# relay-v1.net
KiCad netlist of a schematic drawn in EAGLE
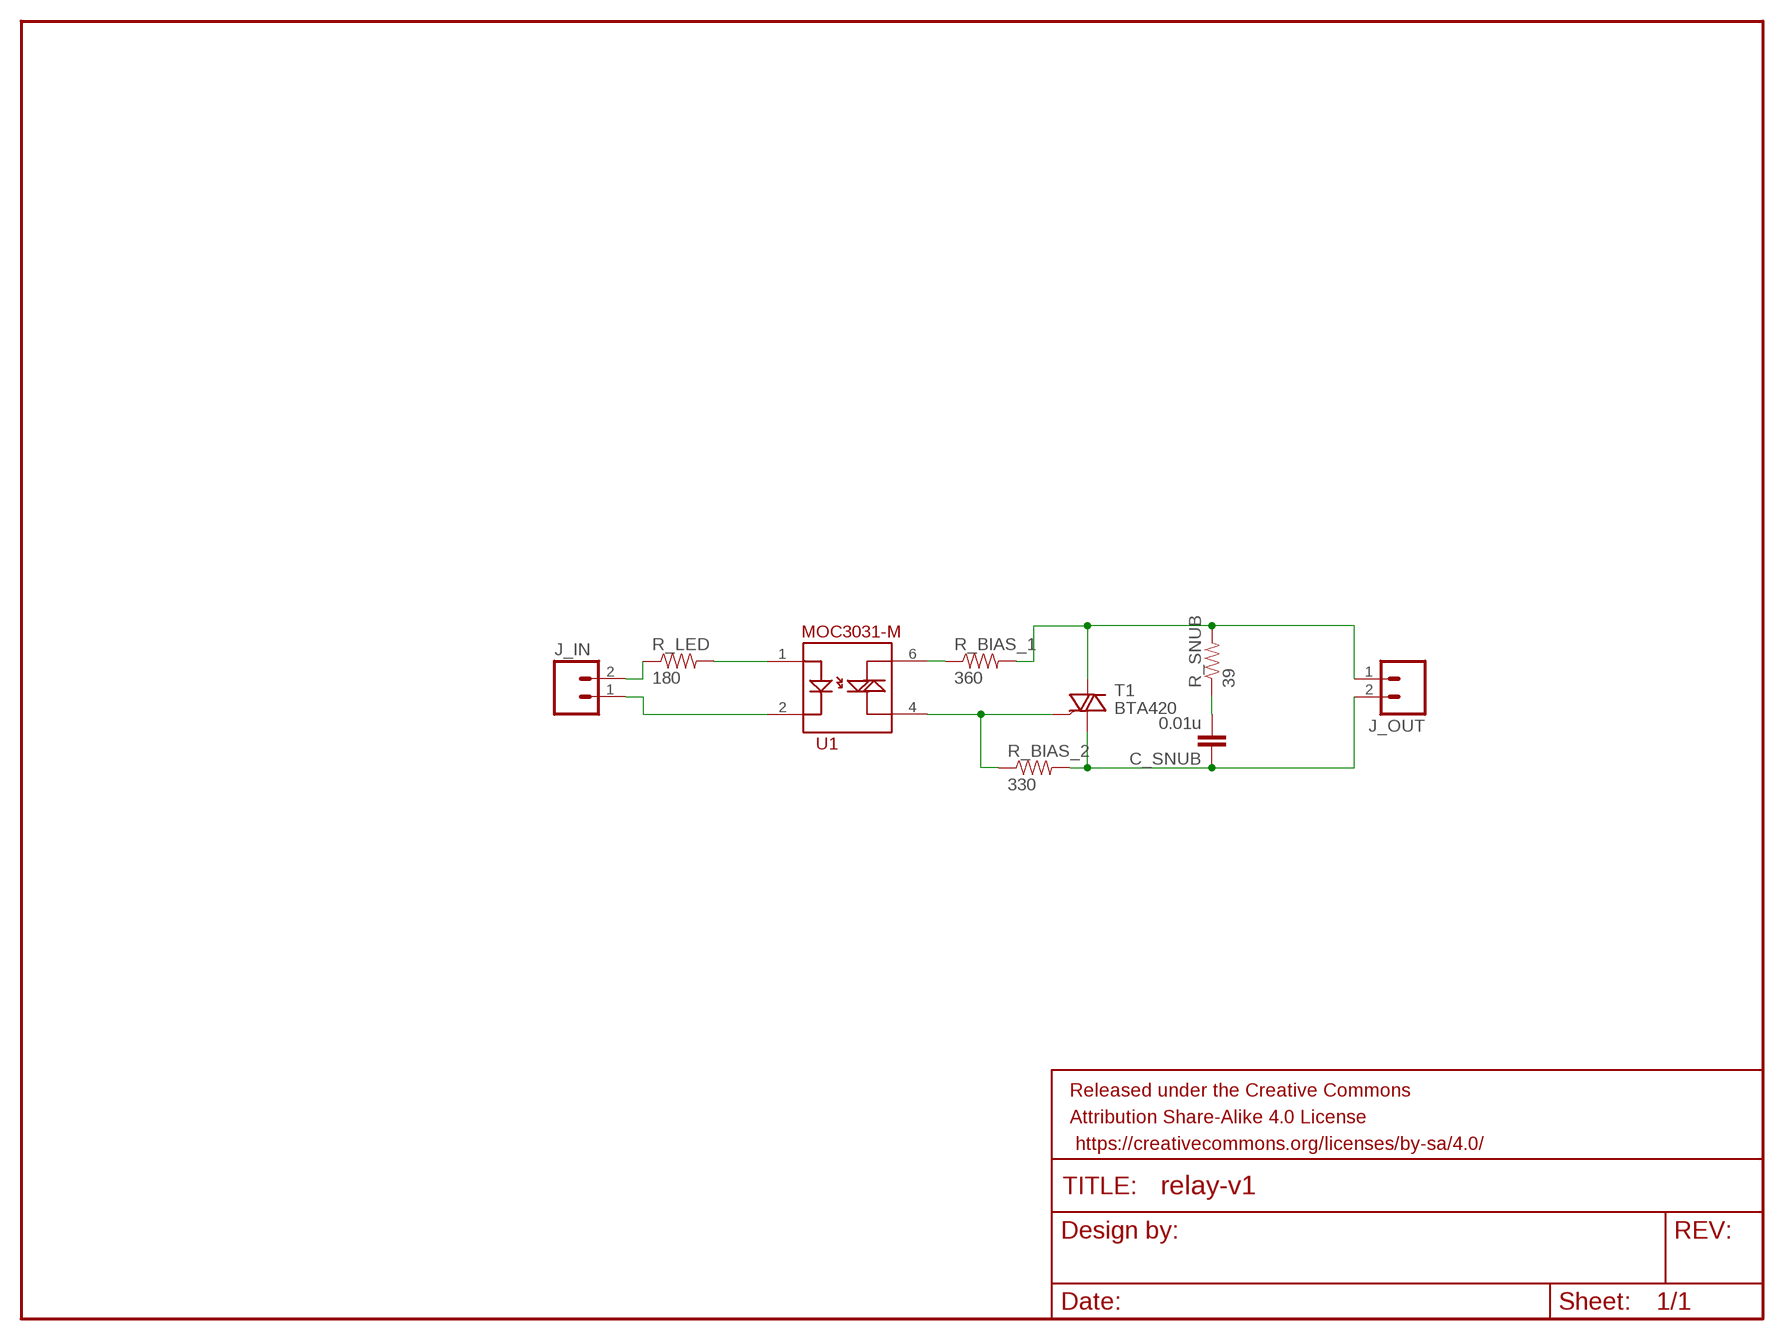
[diagram p0: schematic, sheet 1]

(export (version "E")
  (design (tool "Eeschema 10.0.6"))
  (components
    (comp (ref "C_SNUB")
      (value "0.01u")
      (footprint "eagle-import:CAP-PTH-SMALLEZ")
      (libsource (lib "eagle-import") (part "CAPEZ"))
    )
    (comp (ref "FRAME1")
      (value "FRAME-LETTERNO_PACKAGE")
      (footprint "eagle-import:DUMMY")
      (fields (field (name "DESIGNER") "Nobody"))
      (libsource (lib "eagle-import") (part "FRAME-LETTERNO_PACKAGE"))
    )
    (comp (ref "J_IN")
      (value "M02PTH")
      (footprint "eagle-import:1X02")
      (libsource (lib "eagle-import") (part "M02PTH"))
    )
    (comp (ref "J_OUT")
      (value "M025MM")
      (footprint "eagle-import:SCREWTERMINAL-5MM-2")
      (libsource (lib "eagle-import") (part "M025MM"))
    )
    (comp (ref "R_BIAS_1")
      (value "360")
      (footprint "eagle-import:AXIAL-0.4")
      (libsource (lib "eagle-import") (part "RESISTORPTH-1/4W"))
    )
    (comp (ref "R_BIAS_2")
      (value "330")
      (footprint "eagle-import:AXIAL-0.4")
      (libsource (lib "eagle-import") (part "RESISTORPTH-1/4W"))
    )
    (comp (ref "R_LED")
      (value "180")
      (footprint "eagle-import:AXIAL-0.4")
      (libsource (lib "eagle-import") (part "RESISTORPTH-1/4W"))
    )
    (comp (ref "R_SNUB")
      (value "39")
      (footprint "eagle-import:AXIAL-0.4")
      (libsource (lib "eagle-import") (part "RESISTORPTH-1/4W"))
    )
    (comp (ref "T1")
      (value "BTA420")
      (footprint "eagle-import:TO220BV")
      (libsource (lib "eagle-import") (part "BT138-V"))
    )
    (comp (ref "U1")
      (value "MOC3063M")
      (footprint "eagle-import:DIL06")
      (libsource (lib "eagle-import") (part "MOC3031-M"))
    )
  )
  (nets
    (net (code "1") (name "Net-(J_IN-Pad1)") (class "Default")
      (node (ref "J_IN") (pin "1") (pinfunction "1_1") (pintype "passive"))
      (node (ref "U1") (pin "2") (pinfunction "2_2") (pintype "bidirectional"))
    )
    (net (code "2") (name "Net-(R_BIAS_1-1)") (class "Default")
      (node (ref "R_BIAS_1") (pin "P$1") (pinfunction "1_P$1") (pintype "passive"))
      (node (ref "U1") (pin "6") (pinfunction "6_6") (pintype "bidirectional"))
    )
    (net (code "3") (name "Net-(R_BIAS_1-2)") (class "Default")
      (node (ref "J_OUT") (pin "1") (pinfunction "1_1") (pintype "passive"))
      (node (ref "R_BIAS_1") (pin "P$2") (pinfunction "2_P$2") (pintype "passive"))
      (node (ref "R_SNUB") (pin "P$2") (pinfunction "2_P$2") (pintype "passive"))
      (node (ref "T1") (pin "T2") (pinfunction "A2_T2") (pintype "passive"))
    )
    (net (code "4") (name "Net-(R_BIAS_2-1)") (class "Default")
      (node (ref "R_BIAS_2") (pin "P$1") (pinfunction "1_P$1") (pintype "passive"))
      (node (ref "T1") (pin "G") (pinfunction "G_G") (pintype "passive"))
      (node (ref "U1") (pin "4") (pinfunction "4_4") (pintype "bidirectional"))
    )
    (net (code "5") (name "Net-(R_BIAS_2-2)") (class "Default")
      (node (ref "C_SNUB") (pin "1") (pinfunction "1_1") (pintype "passive"))
      (node (ref "J_OUT") (pin "2") (pinfunction "2_2") (pintype "passive"))
      (node (ref "R_BIAS_2") (pin "P$2") (pinfunction "2_P$2") (pintype "passive"))
      (node (ref "T1") (pin "T1") (pinfunction "A1_T1") (pintype "passive"))
    )
    (net (code "6") (name "Net-(R_LED-1)") (class "Default")
      (node (ref "J_IN") (pin "2") (pinfunction "2_2") (pintype "passive"))
      (node (ref "R_LED") (pin "P$1") (pinfunction "1_P$1") (pintype "passive"))
    )
    (net (code "7") (name "Net-(R_LED-2)") (class "Default")
      (node (ref "R_LED") (pin "P$2") (pinfunction "2_P$2") (pintype "passive"))
      (node (ref "U1") (pin "1") (pinfunction "1_1") (pintype "bidirectional"))
    )
    (net (code "8") (name "Net-(R_SNUB-1)") (class "Default")
      (node (ref "C_SNUB") (pin "2") (pinfunction "2_2") (pintype "passive"))
      (node (ref "R_SNUB") (pin "P$1") (pinfunction "1_P$1") (pintype "passive"))
    )
  )
)
